# 03_MCU.net
KiCad netlist of a schematic drawn in Altium Designer
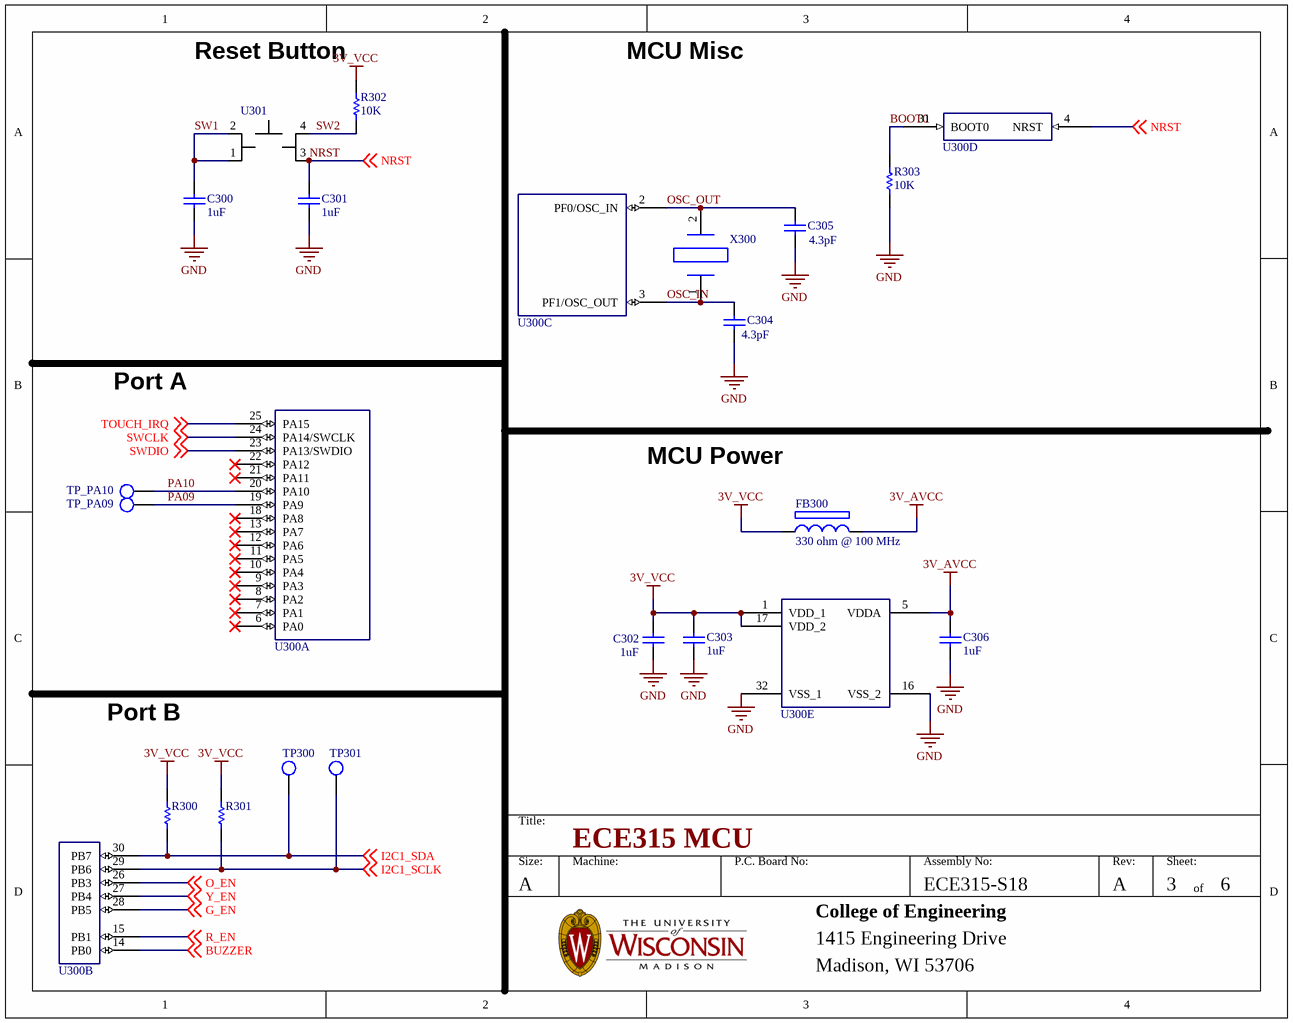
[diagram p0: 03_MCU.SchDoc]

(export (version "E")
  (design (tool "Eeschema 10.0.6"))
  (components
    (comp (ref "C300")
      (value "CAP_0805_U_001.00")
      (footprint "CAP_0805")
      (description "CAP CER 1UF 16V 10% X7R 0805")
      (fields
        (field (name "MANUFACTURER") "Yageo")
        (field (name "MANUFACTURER PART NUMBER") "CC0805KKX7R7BB105")
        (field (name "SUPPLIER PART NUMBER 1") "1uF")
      )
      (libsource (lib "ece315") (part "CAP_0805_U_001.00"))
    )
    (comp (ref "C301")
      (value "CAP_0805_U_001.00")
      (footprint "CAP_0805")
      (description "CAP CER 1UF 16V 10% X7R 0805")
      (fields
        (field (name "MANUFACTURER") "Yageo")
        (field (name "MANUFACTURER PART NUMBER") "CC0805KKX7R7BB105")
        (field (name "SUPPLIER PART NUMBER 1") "1uF")
      )
      (libsource (lib "ece315") (part "CAP_0805_U_001.00"))
    )
    (comp (ref "C302")
      (value "CAP_0805_U_001.00")
      (footprint "CAP_0805")
      (description "CAP CER 1UF 16V 10% X7R 0805")
      (fields
        (field (name "MANUFACTURER") "Yageo")
        (field (name "MANUFACTURER PART NUMBER") "CC0805KKX7R7BB105")
        (field (name "SUPPLIER PART NUMBER 1") "1uF")
      )
      (libsource (lib "ece315") (part "CAP_0805_U_001.00"))
    )
    (comp (ref "C303")
      (value "CAP_0805_U_001.00")
      (footprint "CAP_0805")
      (description "CAP CER 1UF 16V 10% X7R 0805")
      (fields
        (field (name "MANUFACTURER") "Yageo")
        (field (name "MANUFACTURER PART NUMBER") "CC0805KKX7R7BB105")
        (field (name "SUPPLIER PART NUMBER 1") "1uF")
      )
      (libsource (lib "ece315") (part "CAP_0805_U_001.00"))
    )
    (comp (ref "C304")
      (value "4.3pF")
      (footprint "CAP_0805")
      (description "CAP CER 4.3PF 100V NP0 0805")
      (fields
        (field (name "MANUFACTURER") "AVX Corporation")
        (field (name "MANUFACTURER PART NUMBER") "08051A4R3BAT2A")
      )
      (libsource (lib "ece315") (part "CAP_0805_P_004.30"))
    )
    (comp (ref "C305")
      (value "4.3pF")
      (footprint "CAP_0805")
      (description "CAP CER 4.3PF 100V NP0 0805")
      (fields
        (field (name "MANUFACTURER") "AVX Corporation")
        (field (name "MANUFACTURER PART NUMBER") "08051A4R3BAT2A")
      )
      (libsource (lib "ece315") (part "CAP_0805_P_004.30"))
    )
    (comp (ref "C306")
      (value "CAP_0805_U_001.00")
      (footprint "CAP_0805")
      (description "CAP CER 1UF 16V 10% X7R 0805")
      (fields
        (field (name "MANUFACTURER") "Yageo")
        (field (name "MANUFACTURER PART NUMBER") "CC0805KKX7R7BB105")
        (field (name "SUPPLIER PART NUMBER 1") "1uF")
      )
      (libsource (lib "ece315") (part "CAP_0805_U_001.00"))
    )
    (comp (ref "FB300")
      (value "330 ohm @ 100 MHz")
      (footprint "FB_0805")
      (fields
        (field (name "MANUFACTURER") "TDK Corporation")
        (field (name "MANUFACTURER PART NUMBER") "MPZ2012S331AT000")
      )
      (libsource (lib "ece315") (part "FB 330 ohm @ 100 MHz"))
    )
    (comp (ref "R300")
      (value "10K")
      (footprint "RES_0805")
      (description "RES SMD 10K OHM 1% 1/8W 0805")
      (fields
        (field (name "MANUFACTURER") "Yageo")
        (field (name "MANUFACTURER PART NUMBER") "RC0805FR-0710KL")
      )
      (libsource (lib "ece315") (part "RES_0805_K_010.00"))
    )
    (comp (ref "R301")
      (value "10K")
      (footprint "RES_0805")
      (description "RES SMD 10K OHM 1% 1/8W 0805")
      (fields
        (field (name "MANUFACTURER") "Yageo")
        (field (name "MANUFACTURER PART NUMBER") "RC0805FR-0710KL")
      )
      (libsource (lib "ece315") (part "RES_0805_K_010.00"))
    )
    (comp (ref "R302")
      (value "10K")
      (footprint "RES_0805")
      (description "RES SMD 10K OHM 1% 1/8W 0805")
      (fields
        (field (name "MANUFACTURER") "Yageo")
        (field (name "MANUFACTURER PART NUMBER") "RC0805FR-0710KL")
        (field (name "SUPPLIER PART NUMBER 1") "10K")
      )
      (libsource (lib "ece315") (part "RES_0805_K_010.00"))
    )
    (comp (ref "R303")
      (value "10K")
      (footprint "RES_0805")
      (description "RES SMD 10K OHM 1% 1/8W 0805")
      (fields
        (field (name "MANUFACTURER") "Yageo")
        (field (name "MANUFACTURER PART NUMBER") "RC0805FR-0710KL")
        (field (name "SUPPLIER PART NUMBER 1") "10K")
      )
      (libsource (lib "ece315") (part "RES_0805_K_010.00"))
    )
    (comp (ref "TP300")
      (value "TP_1206")
      (footprint "TP-SMC-1206")
      (description "Test Point SMD 1206")
      (fields
        (field (name "MANUFACTURER") "TE Connectivity (Tyco Electronics)")
        (field (name "MANUFACTURER PART NUMBER") "1625854-1")
      )
      (libsource (lib "ece315") (part "TP_1206"))
    )
    (comp (ref "TP301")
      (value "TP_1206")
      (footprint "TP-SMC-1206")
      (description "Test Point SMD 1206")
      (fields
        (field (name "MANUFACTURER") "TE Connectivity (Tyco Electronics)")
        (field (name "MANUFACTURER PART NUMBER") "1625854-1")
      )
      (libsource (lib "ece315") (part "TP_1206"))
    )
    (comp (ref "TP_PA09")
      (value "TP_1206")
      (footprint "TP-SMC-1206")
      (description "Test Point SMD 1206")
      (fields
        (field (name "MANUFACTURER") "TE Connectivity (Tyco Electronics)")
        (field (name "MANUFACTURER PART NUMBER") "1625854-1")
      )
      (libsource (lib "ece315") (part "TP_1206"))
    )
    (comp (ref "TP_PA10")
      (value "TP_1206")
      (footprint "TP-SMC-1206")
      (description "Test Point SMD 1206")
      (fields
        (field (name "MANUFACTURER") "TE Connectivity (Tyco Electronics)")
        (field (name "MANUFACTURER PART NUMBER") "1625854-1")
      )
      (libsource (lib "ece315") (part "TP_1206"))
    )
    (comp (ref "U300")
      (value "IC_STM32F303K8T6_1")
      (footprint "IC_STM32FM")
      (libsource (lib "ece315") (part "IC_STM32F303K8T6_1"))
    )
    (comp (ref "U301")
      (value "SW_6mm_6mm_SMT")
      (footprint "SW_6mm_6mm_SMT")
      (description "SWITCH TACTILE SPST-NO 0.05A 12V")
      (fields
        (field (name "MANUFACTURER") "C&K")
        (field (name "MANUFACTURER PART NUMBER") "PTS645SK50SMTR92 LFS")
      )
      (libsource (lib "ece315") (part "SW_6mm_6mm_SMT"))
    )
    (comp (ref "X300")
      (value "32.7680KHZ 12.5PF")
      (footprint "NX3215SA-32.768K-STD-MUA-8")
      (description "CRYSTAL 32.768KHZ 12.5PF SMD")
      (fields
        (field (name "MANUFACTURER") "Nihon Dempa Kogyo (NDK)")
        (field (name "MANUFACTURER PART NUMBER") "NX3215SA-32.768K-STD-MUA-8")
      )
      (libsource (lib "ece315") (part "CRYSTAL_NX3215SA-32.768K"))
    )
  )
  (nets
    (net (code "1") (name "/BOOT0") (class "Default")
      (node (ref "R303") (pin "2") (pinfunction "2_2") (pintype "passive"))
      (node (ref "U300") (pin "31") (pinfunction "BOOT0_31") (pintype "input"))
    )
    (net (code "2") (name "/OSC_IN") (class "Default")
      (node (ref "C304") (pin "2") (pinfunction "2_2") (pintype "passive"))
      (node (ref "U300") (pin "3") (pinfunction "PF1/OSC_OUT_3") (pintype "bidirectional"))
      (node (ref "X300") (pin "1") (pinfunction "1_1") (pintype "passive"))
    )
    (net (code "3") (name "/OSC_OUT") (class "Default")
      (node (ref "C305") (pin "2") (pinfunction "2_2") (pintype "passive"))
      (node (ref "U300") (pin "2") (pinfunction "PF0/OSC_IN_2") (pintype "bidirectional"))
      (node (ref "X300") (pin "2") (pinfunction "2_2") (pintype "passive"))
    )
    (net (code "4") (name "/PA09") (class "Default")
      (node (ref "TP_PA09") (pin "1") (pintype "passive"))
      (node (ref "U300") (pin "19") (pinfunction "PA9_19") (pintype "bidirectional"))
    )
    (net (code "5") (name "/PA10") (class "Default")
      (node (ref "TP_PA10") (pin "1") (pintype "passive"))
      (node (ref "U300") (pin "20") (pinfunction "PA10_20") (pintype "bidirectional"))
    )
    (net (code "6") (name "/SW1") (class "Default")
      (node (ref "C300") (pin "1") (pinfunction "1_1") (pintype "passive"))
      (node (ref "U301") (pin "1") (pinfunction "1_1") (pintype "passive"))
      (node (ref "U301") (pin "2") (pinfunction "2_2") (pintype "passive"))
    )
    (net (code "7") (name "/SW2") (class "Default")
      (node (ref "R302") (pin "1") (pinfunction "1_1") (pintype "passive"))
      (node (ref "U301") (pin "4") (pinfunction "VCCIO_4") (pintype "passive"))
    )
    (net (code "8") (name "3V_AVCC") (class "Default")
      (node (ref "C306") (pin "1") (pinfunction "1_1") (pintype "passive"))
      (node (ref "FB300") (pin "2") (pinfunction "2_2") (pintype "passive"))
      (node (ref "U300") (pin "5") (pinfunction "VDDA_5") (pintype "power_in"))
    )
    (net (code "9") (name "3V_VCC") (class "Default")
      (node (ref "C302") (pin "1") (pinfunction "1_1") (pintype "passive"))
      (node (ref "C303") (pin "1") (pinfunction "1_1") (pintype "passive"))
      (node (ref "FB300") (pin "1") (pinfunction "1_1") (pintype "passive"))
      (node (ref "R300") (pin "2") (pinfunction "2_2") (pintype "passive"))
      (node (ref "R301") (pin "2") (pinfunction "2_2") (pintype "passive"))
      (node (ref "R302") (pin "2") (pinfunction "2_2") (pintype "passive"))
      (node (ref "U300") (pin "1") (pinfunction "VDD_1_1") (pintype "passive"))
      (node (ref "U300") (pin "17") (pinfunction "VDD_2_17") (pintype "power_in"))
    )
    (net (code "10") (name "BUZZER") (class "Default")
      (node (ref "U300") (pin "14") (pinfunction "PB0_14") (pintype "bidirectional"))
    )
    (net (code "11") (name "GND") (class "Default")
      (node (ref "C300") (pin "2") (pinfunction "2_2") (pintype "passive"))
      (node (ref "C301") (pin "2") (pinfunction "2_2") (pintype "passive"))
      (node (ref "C302") (pin "2") (pinfunction "2_2") (pintype "passive"))
      (node (ref "C303") (pin "2") (pinfunction "2_2") (pintype "passive"))
      (node (ref "C304") (pin "1") (pinfunction "1_1") (pintype "passive"))
      (node (ref "C305") (pin "1") (pinfunction "1_1") (pintype "passive"))
      (node (ref "C306") (pin "2") (pinfunction "2_2") (pintype "passive"))
      (node (ref "R303") (pin "1") (pinfunction "1_1") (pintype "passive"))
      (node (ref "U300") (pin "16") (pinfunction "VSS_2_16") (pintype "power_in"))
      (node (ref "U300") (pin "32") (pinfunction "VSS_1_32") (pintype "power_in"))
    )
    (net (code "12") (name "G_EN") (class "Default")
      (node (ref "U300") (pin "28") (pinfunction "PB5_28") (pintype "bidirectional"))
    )
    (net (code "13") (name "I2C1_SCLK") (class "Default")
      (node (ref "R301") (pin "1") (pinfunction "1_1") (pintype "passive"))
      (node (ref "TP301") (pin "1") (pintype "passive"))
      (node (ref "U300") (pin "29") (pinfunction "PB6_29") (pintype "bidirectional"))
    )
    (net (code "14") (name "I2C1_SDA") (class "Default")
      (node (ref "R300") (pin "1") (pinfunction "1_1") (pintype "passive"))
      (node (ref "TP300") (pin "1") (pintype "passive"))
      (node (ref "U300") (pin "30") (pinfunction "PB7_30") (pintype "bidirectional"))
    )
    (net (code "15") (name "NRST") (class "Default")
      (node (ref "C301") (pin "1") (pinfunction "1_1") (pintype "passive"))
      (node (ref "U300") (pin "4") (pinfunction "NRST_4") (pintype "input"))
      (node (ref "U301") (pin "3") (pinfunction "3_3") (pintype "passive"))
    )
    (net (code "16") (name "O_EN") (class "Default")
      (node (ref "U300") (pin "26") (pinfunction "PB3_26") (pintype "bidirectional"))
    )
    (net (code "17") (name "R_EN") (class "Default")
      (node (ref "U300") (pin "15") (pinfunction "PB1_15") (pintype "bidirectional"))
    )
    (net (code "18") (name "SWCLK") (class "Default")
      (node (ref "U300") (pin "24") (pinfunction "PA14/SWCLK_24") (pintype "bidirectional"))
    )
    (net (code "19") (name "SWDIO") (class "Default")
      (node (ref "U300") (pin "23") (pinfunction "PA13/SWDIO_23") (pintype "bidirectional"))
    )
    (net (code "20") (name "TOUCH_IRQ") (class "Default")
      (node (ref "U300") (pin "25") (pinfunction "PA15_25") (pintype "bidirectional"))
    )
    (net (code "21") (name "Y_EN") (class "Default")
      (node (ref "U300") (pin "27") (pinfunction "PB4_27") (pintype "bidirectional"))
    )
    (net (code "22") (name "unconnected-(U300A-PA0-Pad6)") (class "Default")
      (node (ref "U300") (pin "6") (pinfunction "PA0_6") (pintype "bidirectional+no_connect"))
    )
    (net (code "23") (name "unconnected-(U300A-PA1-Pad7)") (class "Default")
      (node (ref "U300") (pin "7") (pinfunction "PA1_7") (pintype "bidirectional+no_connect"))
    )
    (net (code "24") (name "unconnected-(U300A-PA2-Pad8)") (class "Default")
      (node (ref "U300") (pin "8") (pinfunction "PA2_8") (pintype "bidirectional+no_connect"))
    )
    (net (code "25") (name "unconnected-(U300A-PA3-Pad9)") (class "Default")
      (node (ref "U300") (pin "9") (pinfunction "PA3_9") (pintype "bidirectional+no_connect"))
    )
    (net (code "26") (name "unconnected-(U300A-PA4-Pad10)") (class "Default")
      (node (ref "U300") (pin "10") (pinfunction "PA4_10") (pintype "bidirectional+no_connect"))
    )
    (net (code "27") (name "unconnected-(U300A-PA5-Pad11)") (class "Default")
      (node (ref "U300") (pin "11") (pinfunction "PA5_11") (pintype "bidirectional+no_connect"))
    )
    (net (code "28") (name "unconnected-(U300A-PA6-Pad12)") (class "Default")
      (node (ref "U300") (pin "12") (pinfunction "PA6_12") (pintype "bidirectional+no_connect"))
    )
    (net (code "29") (name "unconnected-(U300A-PA7-Pad13)") (class "Default")
      (node (ref "U300") (pin "13") (pinfunction "PA7_13") (pintype "bidirectional+no_connect"))
    )
    (net (code "30") (name "unconnected-(U300A-PA8-Pad18)") (class "Default")
      (node (ref "U300") (pin "18") (pinfunction "PA8_18") (pintype "bidirectional+no_connect"))
    )
    (net (code "31") (name "unconnected-(U300A-PA11-Pad21)") (class "Default")
      (node (ref "U300") (pin "21") (pinfunction "PA11_21") (pintype "bidirectional+no_connect"))
    )
    (net (code "32") (name "unconnected-(U300A-PA12-Pad22)") (class "Default")
      (node (ref "U300") (pin "22") (pinfunction "PA12_22") (pintype "bidirectional+no_connect"))
    )
  )
)
